# Schematic.net
KiCad netlist of a schematic drawn in EAGLE
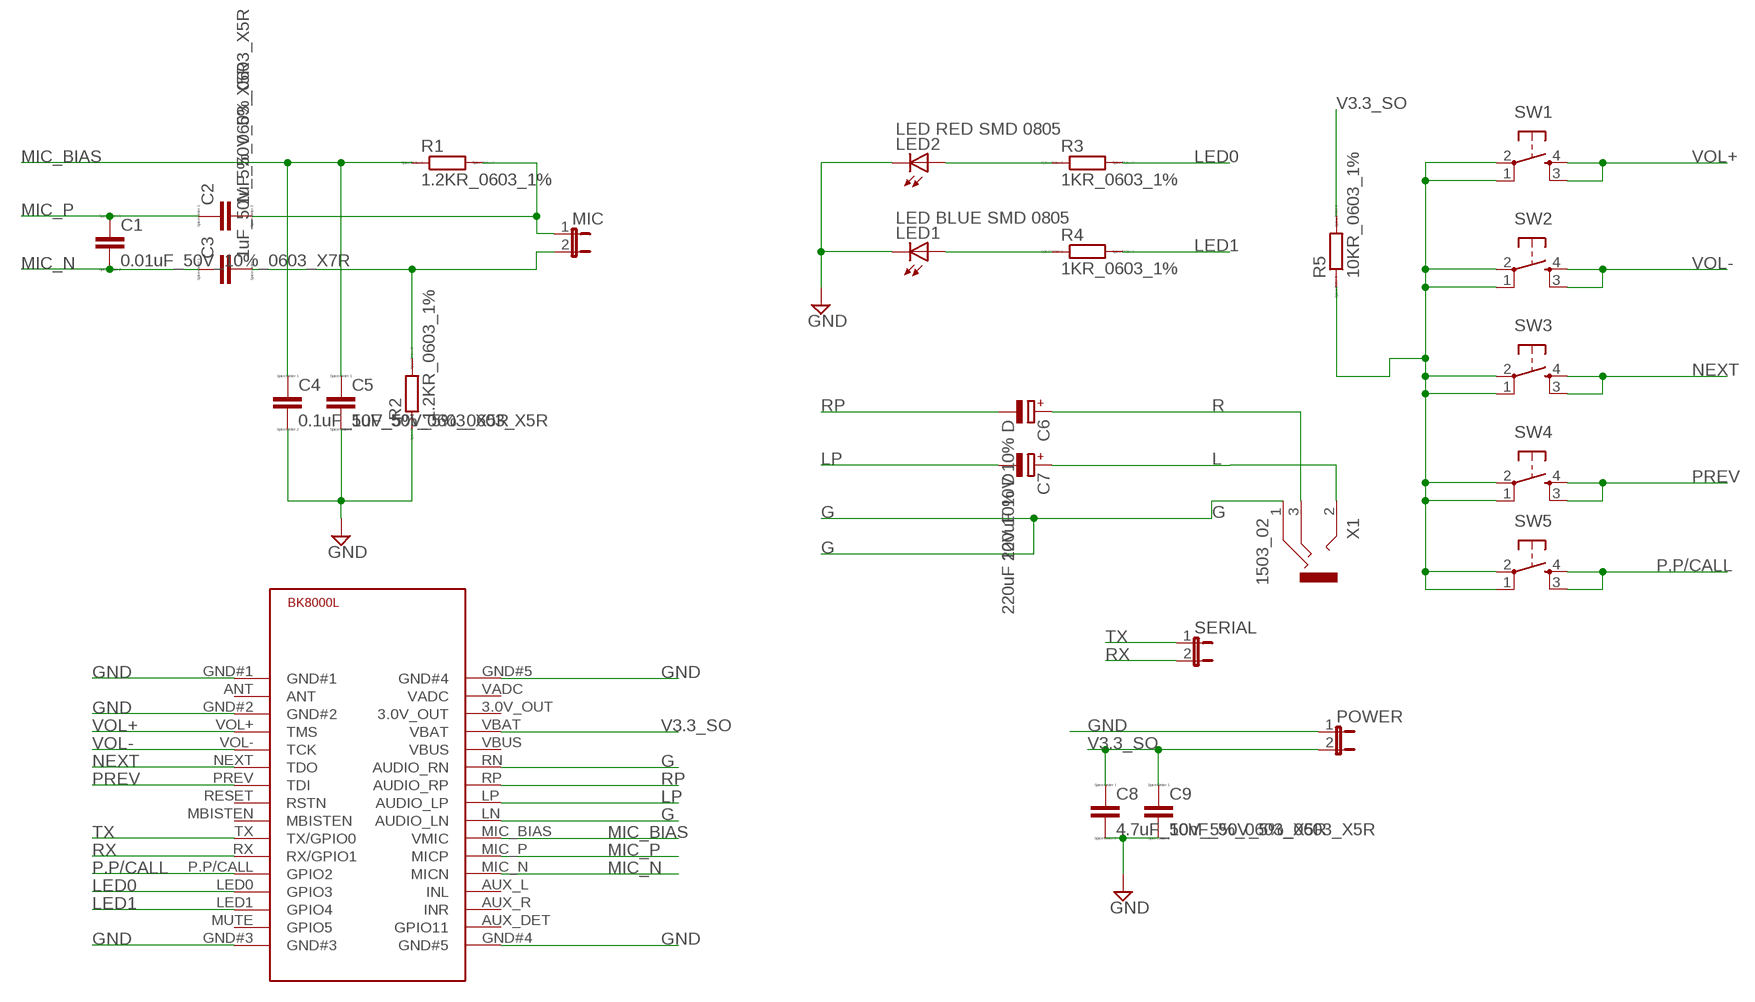
[diagram p0: schematic, sheet 1]

(export (version "E")
  (design (tool "Eeschema 10.0.6"))
  (components
    (comp (ref "C1")
      (value "0.01uF_50V_10%_0603_X7R")
      (footprint "eagle-import:C0603")
      (libsource (lib "eagle-import") (part "CC0603"))
    )
    (comp (ref "C2")
      (value "1uF_50V_5%_0603_X5R")
      (footprint "eagle-import:C0603")
      (libsource (lib "eagle-import") (part "CC0603"))
    )
    (comp (ref "C3")
      (value "1uF_50V_5%_0603_X5R")
      (footprint "eagle-import:C0603")
      (libsource (lib "eagle-import") (part "CC0603"))
    )
    (comp (ref "C4")
      (value "0.1uF_50V_5%_0603_X5R")
      (footprint "eagle-import:C0603")
      (libsource (lib "eagle-import") (part "CC0603"))
    )
    (comp (ref "C5")
      (value "1uF_50V_5%_0603_X5R")
      (footprint "eagle-import:C0603")
      (libsource (lib "eagle-import") (part "CC0603"))
    )
    (comp (ref "C6")
      (value "220uF 10V 10% D")
      (footprint "eagle-import:SMC_D")
      (libsource (lib "eagle-import") (part "CPOL-EUSMCD"))
    )
    (comp (ref "C7")
      (value "220uF 10V 10% D")
      (footprint "eagle-import:SMC_D")
      (libsource (lib "eagle-import") (part "CPOL-EUSMCD"))
    )
    (comp (ref "C8")
      (value "4.7uF_50V_5%_0603_X5R")
      (footprint "eagle-import:C0603")
      (libsource (lib "eagle-import") (part "CC0603"))
    )
    (comp (ref "C9")
      (value "10nF_50V_5%_0603_X5R")
      (footprint "eagle-import:C0603")
      (libsource (lib "eagle-import") (part "CC0603"))
    )
    (comp (ref "LED1")
      (value "LED BLUE SMD 0805")
      (footprint "eagle-import:CHIP-LED0805")
      (libsource (lib "eagle-import") (part "LEDCHIP-LED0805"))
    )
    (comp (ref "LED2")
      (value "LED RED SMD 0805")
      (footprint "eagle-import:CHIP-LED0805")
      (libsource (lib "eagle-import") (part "LEDCHIP-LED0805"))
    )
    (comp (ref "MIC")
      (value "JP1E")
      (footprint "eagle-import:JP1")
      (libsource (lib "eagle-import") (part "JP1E"))
    )
    (comp (ref "POWER")
      (value "JP1E")
      (footprint "eagle-import:JP1")
      (libsource (lib "eagle-import") (part "JP1E"))
    )
    (comp (ref "R1")
      (value "1.2KR_0603_1%")
      (footprint "eagle-import:R0603")
      (libsource (lib "eagle-import") (part "RR0603"))
    )
    (comp (ref "R2")
      (value "1.2KR_0603_1%")
      (footprint "eagle-import:R0603")
      (libsource (lib "eagle-import") (part "RR0603"))
    )
    (comp (ref "R3")
      (value "1KR_0603_1%")
      (footprint "eagle-import:R0603")
      (libsource (lib "eagle-import") (part "RR0603"))
    )
    (comp (ref "R4")
      (value "1KR_0603_1%")
      (footprint "eagle-import:R0603")
      (libsource (lib "eagle-import") (part "RR0603"))
    )
    (comp (ref "R5")
      (value "10KR_0603_1%")
      (footprint "eagle-import:R0603")
      (libsource (lib "eagle-import") (part "RR0603"))
    )
    (comp (ref "SERIAL")
      (value "JP1E")
      (footprint "eagle-import:JP1")
      (libsource (lib "eagle-import") (part "JP1E"))
    )
    (comp (ref "SW1")
      (value "10-XX4X4SMD")
      (footprint "eagle-import:BT4X4")
      (libsource (lib "eagle-import") (part "10-XX4X4SMD"))
    )
    (comp (ref "SW2")
      (value "10-XX4X4SMD")
      (footprint "eagle-import:BT4X4")
      (libsource (lib "eagle-import") (part "10-XX4X4SMD"))
    )
    (comp (ref "SW3")
      (value "10-XX4X4SMD")
      (footprint "eagle-import:BT4X4")
      (libsource (lib "eagle-import") (part "10-XX4X4SMD"))
    )
    (comp (ref "SW4")
      (value "10-XX4X4SMD")
      (footprint "eagle-import:BT4X4")
      (libsource (lib "eagle-import") (part "10-XX4X4SMD"))
    )
    (comp (ref "SW5")
      (value "10-XX4X4SMD")
      (footprint "eagle-import:BT4X4")
      (libsource (lib "eagle-import") (part "10-XX4X4SMD"))
    )
    (comp (ref "U$1")
      (value "BK8000LBK8000L_PAD")
      (footprint "eagle-import:BK8000L")
      (libsource (lib "eagle-import") (part "BK8000LBK8000L_PAD"))
    )
    (comp (ref "X1")
      (value "1503_02")
      (footprint "eagle-import:1503_02")
      (libsource (lib "eagle-import") (part "1503_02"))
    )
  )
  (nets
    (net (code "1") (name "/G") (class "Default")
      (node (ref "U$1") (pin "LN") (pinfunction "AUDIO_LN_LN") (pintype "bidirectional"))
      (node (ref "U$1") (pin "RN") (pinfunction "AUDIO_RN_RN") (pintype "bidirectional"))
      (node (ref "X1") (pin "1") (pinfunction "1_1") (pintype "passive"))
    )
    (net (code "2") (name "/L") (class "Default")
      (node (ref "C7") (pin "+") (pinfunction "+_+") (pintype "passive"))
      (node (ref "X1") (pin "2") (pinfunction "2_2") (pintype "passive"))
    )
    (net (code "3") (name "/LED0") (class "Default")
      (node (ref "R3") (pin "2") (pinfunction "2_2") (pintype "passive"))
      (node (ref "U$1") (pin "LED0") (pinfunction "GPIO3_LED0") (pintype "bidirectional"))
    )
    (net (code "4") (name "/LED1") (class "Default")
      (node (ref "R4") (pin "2") (pinfunction "2_2") (pintype "passive"))
      (node (ref "U$1") (pin "LED1") (pinfunction "GPIO4_LED1") (pintype "bidirectional"))
    )
    (net (code "5") (name "/LP") (class "Default")
      (node (ref "C7") (pin "-") (pinfunction "-_-") (pintype "passive"))
      (node (ref "U$1") (pin "LP") (pinfunction "AUDIO_LP_LP") (pintype "bidirectional"))
    )
    (net (code "6") (name "/MIC_BIAS") (class "Default")
      (node (ref "C4") (pin "1") (pinfunction "1_1") (pintype "passive"))
      (node (ref "C5") (pin "1") (pinfunction "1_1") (pintype "passive"))
      (node (ref "R1") (pin "1") (pinfunction "1_1") (pintype "passive"))
      (node (ref "U$1") (pin "MIC_BIAS") (pinfunction "VMIC_MIC_BIAS") (pintype "bidirectional"))
    )
    (net (code "7") (name "/MIC_N") (class "Default")
      (node (ref "C1") (pin "2") (pinfunction "2_2") (pintype "passive"))
      (node (ref "C3") (pin "1") (pinfunction "1_1") (pintype "passive"))
      (node (ref "U$1") (pin "MIC_N") (pinfunction "MICN_MIC_N") (pintype "bidirectional"))
    )
    (net (code "8") (name "/MIC_P") (class "Default")
      (node (ref "C1") (pin "1") (pinfunction "1_1") (pintype "passive"))
      (node (ref "C2") (pin "1") (pinfunction "1_1") (pintype "passive"))
      (node (ref "U$1") (pin "MIC_P") (pinfunction "MICP_MIC_P") (pintype "bidirectional"))
    )
    (net (code "9") (name "/NEXT") (class "Default")
      (node (ref "SW3") (pin "3") (pinfunction "S1_3") (pintype "passive"))
      (node (ref "SW3") (pin "4") (pinfunction "S_4") (pintype "passive"))
      (node (ref "U$1") (pin "NEXT") (pinfunction "TDO_NEXT") (pintype "bidirectional"))
    )
    (net (code "10") (name "/P.P{slash}CALL") (class "Default")
      (node (ref "SW5") (pin "3") (pinfunction "S1_3") (pintype "passive"))
      (node (ref "SW5") (pin "4") (pinfunction "S_4") (pintype "passive"))
      (node (ref "U$1") (pin "P.P/CALL") (pinfunction "GPIO2_P.P/CALL") (pintype "bidirectional"))
    )
    (net (code "11") (name "/PREV") (class "Default")
      (node (ref "SW4") (pin "3") (pinfunction "S1_3") (pintype "passive"))
      (node (ref "SW4") (pin "4") (pinfunction "S_4") (pintype "passive"))
      (node (ref "U$1") (pin "PREV") (pinfunction "TDI_PREV") (pintype "bidirectional"))
    )
    (net (code "12") (name "/R") (class "Default")
      (node (ref "C6") (pin "+") (pinfunction "+_+") (pintype "passive"))
      (node (ref "X1") (pin "3") (pinfunction "3_3") (pintype "passive"))
    )
    (net (code "13") (name "/RP") (class "Default")
      (node (ref "C6") (pin "-") (pinfunction "-_-") (pintype "passive"))
      (node (ref "U$1") (pin "RP") (pinfunction "AUDIO_RP_RP") (pintype "bidirectional"))
    )
    (net (code "14") (name "/RX") (class "Default")
      (node (ref "SERIAL") (pin "2") (pinfunction "2_2") (pintype "passive"))
      (node (ref "U$1") (pin "RX") (pinfunction "RX/GPIO1_RX") (pintype "bidirectional"))
    )
    (net (code "15") (name "/TX") (class "Default")
      (node (ref "SERIAL") (pin "1") (pinfunction "1_1") (pintype "passive"))
      (node (ref "U$1") (pin "TX") (pinfunction "TX/GPIO0_TX") (pintype "bidirectional"))
    )
    (net (code "16") (name "/V3.3_SO") (class "Default")
      (node (ref "C8") (pin "1") (pinfunction "1_1") (pintype "passive"))
      (node (ref "C9") (pin "1") (pinfunction "1_1") (pintype "passive"))
      (node (ref "POWER") (pin "2") (pinfunction "2_2") (pintype "passive"))
      (node (ref "R5") (pin "2") (pinfunction "2_2") (pintype "passive"))
      (node (ref "U$1") (pin "VBAT") (pinfunction "VBAT_VBAT") (pintype "bidirectional"))
    )
    (net (code "17") (name "/VOL+") (class "Default")
      (node (ref "SW1") (pin "3") (pinfunction "S1_3") (pintype "passive"))
      (node (ref "SW1") (pin "4") (pinfunction "S_4") (pintype "passive"))
      (node (ref "U$1") (pin "VOL+") (pinfunction "TMS_VOL+") (pintype "bidirectional"))
    )
    (net (code "18") (name "/VOL-") (class "Default")
      (node (ref "SW2") (pin "3") (pinfunction "S1_3") (pintype "passive"))
      (node (ref "SW2") (pin "4") (pinfunction "S_4") (pintype "passive"))
      (node (ref "U$1") (pin "VOL-") (pinfunction "TCK_VOL-") (pintype "bidirectional"))
    )
    (net (code "19") (name "GND") (class "Default")
      (node (ref "C4") (pin "2") (pinfunction "2_2") (pintype "passive"))
      (node (ref "C5") (pin "2") (pinfunction "2_2") (pintype "passive"))
      (node (ref "C8") (pin "2") (pinfunction "2_2") (pintype "passive"))
      (node (ref "C9") (pin "2") (pinfunction "2_2") (pintype "passive"))
      (node (ref "LED1") (pin "C") (pinfunction "C_C") (pintype "passive"))
      (node (ref "LED2") (pin "C") (pinfunction "C_C") (pintype "passive"))
      (node (ref "POWER") (pin "1") (pinfunction "1_1") (pintype "passive"))
      (node (ref "R2") (pin "1") (pinfunction "1_1") (pintype "passive"))
      (node (ref "U$1") (pin "GND#1") (pinfunction "GND#1_GND#1") (pintype "bidirectional"))
      (node (ref "U$1") (pin "GND#2") (pinfunction "GND#2_GND#2") (pintype "bidirectional"))
      (node (ref "U$1") (pin "GND#3") (pinfunction "GND#3_GND#3") (pintype "bidirectional"))
      (node (ref "U$1") (pin "GND#4") (pinfunction "GND#5_GND#4") (pintype "bidirectional"))
      (node (ref "U$1") (pin "GND#5") (pinfunction "GND#4_GND#5") (pintype "bidirectional"))
    )
    (net (code "20") (name "Net-(C2-Pad2)") (class "Default")
      (node (ref "C2") (pin "2") (pinfunction "2_2") (pintype "passive"))
      (node (ref "MIC") (pin "1") (pinfunction "1_1") (pintype "passive"))
      (node (ref "R1") (pin "2") (pinfunction "2_2") (pintype "passive"))
    )
    (net (code "21") (name "Net-(C3-Pad2)") (class "Default")
      (node (ref "C3") (pin "2") (pinfunction "2_2") (pintype "passive"))
      (node (ref "MIC") (pin "2") (pinfunction "2_2") (pintype "passive"))
      (node (ref "R2") (pin "2") (pinfunction "2_2") (pintype "passive"))
    )
    (net (code "22") (name "Net-(LED1-PadA)") (class "Default")
      (node (ref "LED1") (pin "A") (pinfunction "A_A") (pintype "passive"))
      (node (ref "R4") (pin "1") (pinfunction "1_1") (pintype "passive"))
    )
    (net (code "23") (name "Net-(LED2-PadA)") (class "Default")
      (node (ref "LED2") (pin "A") (pinfunction "A_A") (pintype "passive"))
      (node (ref "R3") (pin "1") (pinfunction "1_1") (pintype "passive"))
    )
    (net (code "24") (name "Net-(SW1-P)") (class "Default")
      (node (ref "R5") (pin "1") (pinfunction "1_1") (pintype "passive"))
      (node (ref "SW1") (pin "1") (pinfunction "P1_1") (pintype "passive"))
      (node (ref "SW1") (pin "2") (pinfunction "P_2") (pintype "passive"))
      (node (ref "SW2") (pin "1") (pinfunction "P1_1") (pintype "passive"))
      (node (ref "SW2") (pin "2") (pinfunction "P_2") (pintype "passive"))
      (node (ref "SW3") (pin "1") (pinfunction "P1_1") (pintype "passive"))
      (node (ref "SW3") (pin "2") (pinfunction "P_2") (pintype "passive"))
      (node (ref "SW4") (pin "1") (pinfunction "P1_1") (pintype "passive"))
      (node (ref "SW4") (pin "2") (pinfunction "P_2") (pintype "passive"))
      (node (ref "SW5") (pin "1") (pinfunction "P1_1") (pintype "passive"))
      (node (ref "SW5") (pin "2") (pinfunction "P_2") (pintype "passive"))
    )
    (net (code "25") (name "unconnected-(U$1-GPIO5-PadMUTE)") (class "Default")
      (node (ref "U$1") (pin "MUTE") (pinfunction "GPIO5_MUTE") (pintype "bidirectional"))
    )
    (net (code "26") (name "unconnected-(U$1-GPIO11-PadAUX_DET)") (class "Default")
      (node (ref "U$1") (pin "AUX_DET") (pinfunction "GPIO11_AUX_DET") (pintype "bidirectional"))
    )
    (net (code "27") (name "unconnected-(U$1-INL-PadAUX_L)") (class "Default")
      (node (ref "U$1") (pin "AUX_L") (pinfunction "INL_AUX_L") (pintype "bidirectional"))
    )
    (net (code "28") (name "unconnected-(U$1-INR-PadAUX_R)") (class "Default")
      (node (ref "U$1") (pin "AUX_R") (pinfunction "INR_AUX_R") (pintype "bidirectional"))
    )
    (net (code "29") (name "unconnected-(U$1-Pad3.0V_OUT)") (class "Default")
      (node (ref "U$1") (pin "3.0V_OUT") (pinfunction "3.0V_OUT_3.0V_OUT") (pintype "bidirectional"))
    )
    (net (code "30") (name "unconnected-(U$1-PadANT)") (class "Default")
      (node (ref "U$1") (pin "ANT") (pinfunction "ANT_ANT") (pintype "bidirectional"))
    )
    (net (code "31") (name "unconnected-(U$1-PadMBISTEN)") (class "Default")
      (node (ref "U$1") (pin "MBISTEN") (pinfunction "MBISTEN_MBISTEN") (pintype "bidirectional"))
    )
    (net (code "32") (name "unconnected-(U$1-PadVADC)") (class "Default")
      (node (ref "U$1") (pin "VADC") (pinfunction "VADC_VADC") (pintype "bidirectional"))
    )
    (net (code "33") (name "unconnected-(U$1-PadVBUS)") (class "Default")
      (node (ref "U$1") (pin "VBUS") (pinfunction "VBUS_VBUS") (pintype "bidirectional"))
    )
    (net (code "34") (name "unconnected-(U$1-RSTN-PadRESET)") (class "Default")
      (node (ref "U$1") (pin "RESET") (pinfunction "RSTN_RESET") (pintype "bidirectional"))
    )
    (net (code "35") (name "unconnected-(X1-2-Pad2@2)") (class "Default")
      (node (ref "X1") (pin "2@2") (pinfunction "2_2@2") (pintype "passive"))
    )
  )
)
